# sensors.net
KiCad netlist of a schematic drawn in EAGLE
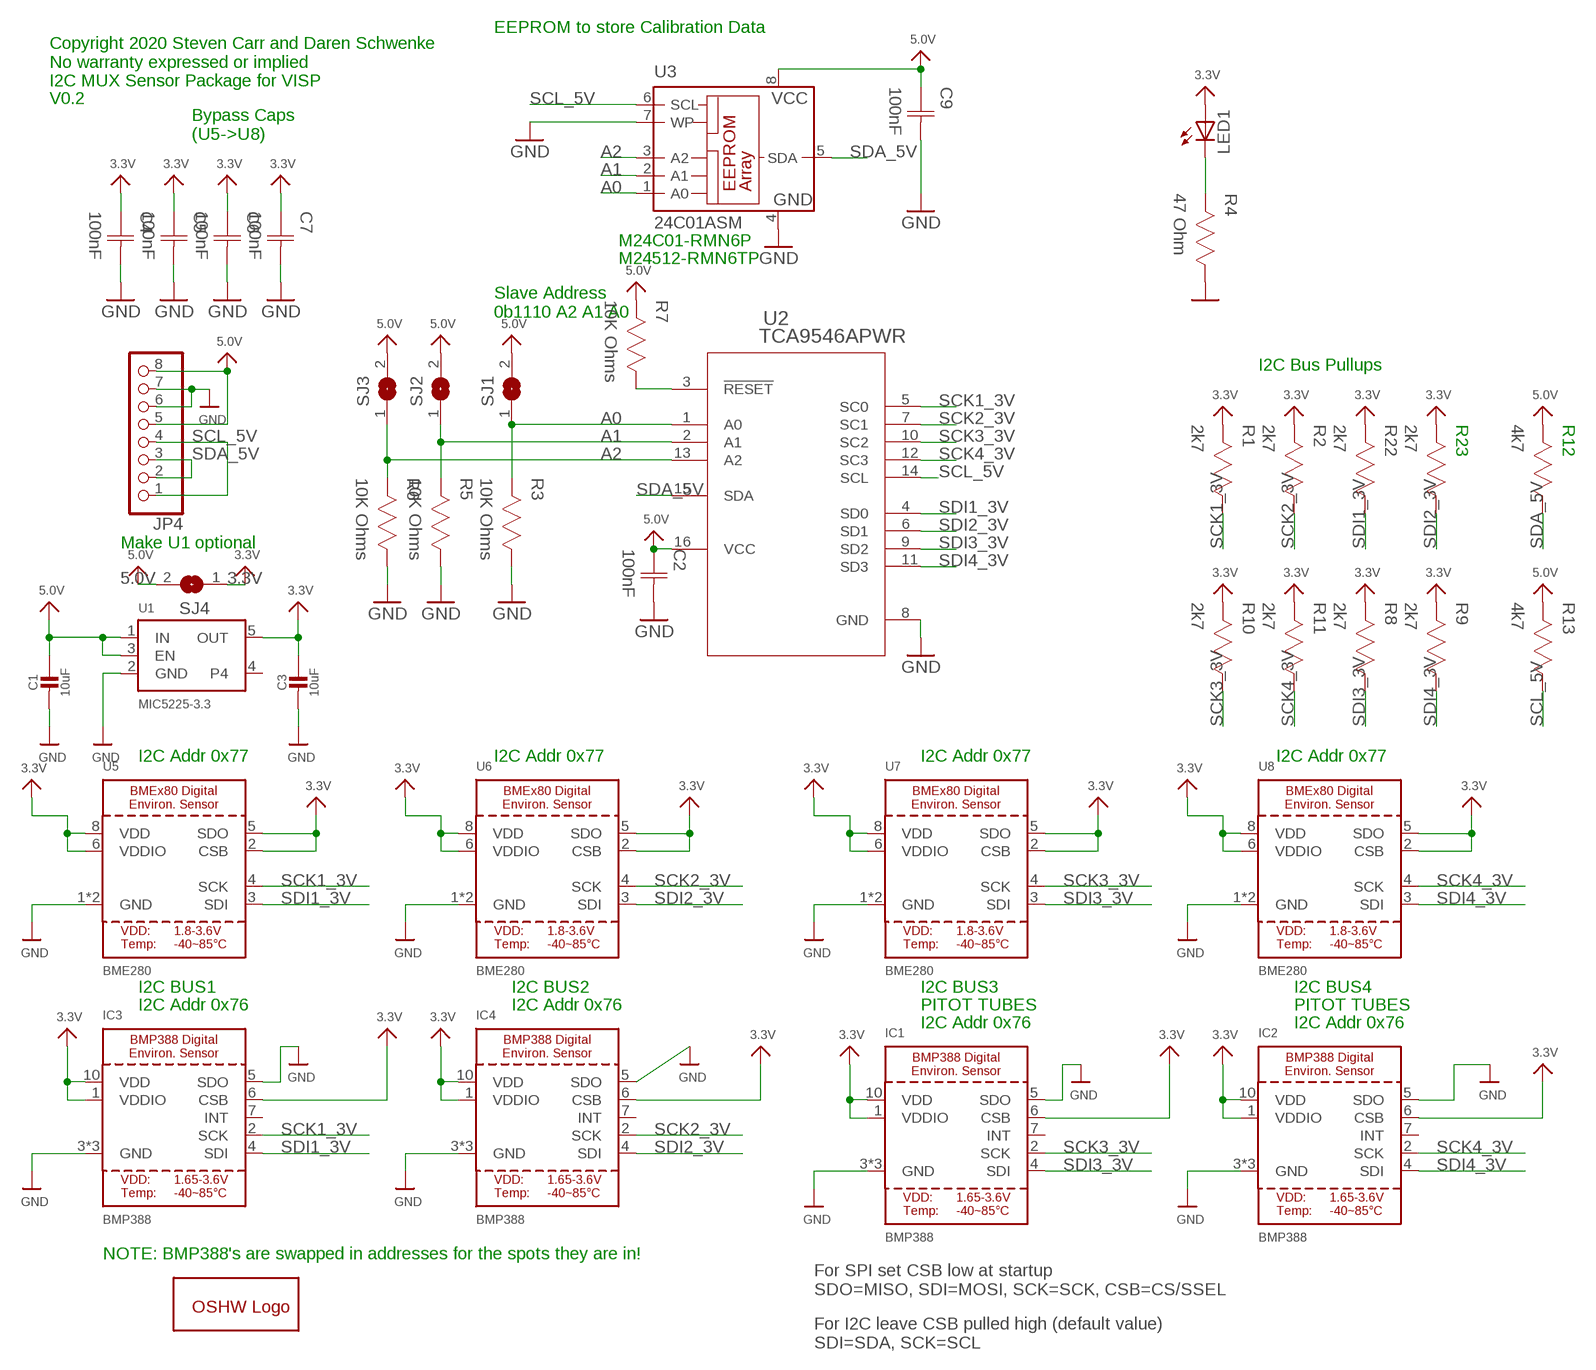
[diagram p0: schematic, sheet 1]

(export (version "E")
  (design (tool "Eeschema 10.0.6"))
  (components
    (comp (ref "C1")
      (value "10uF")
      (footprint "eagle-import:_0805")
      (fields (field (name "MPN") "C1608X5R1A106M080AC"))
      (libsource (lib "eagle-import") (part "CAP_CERAMIC_0805"))
    )
    (comp (ref "C2")
      (value "100nF")
      (footprint "eagle-import:CAP0402")
      (fields (field (name "MPN") "CL10B104KB8NNNC"))
      (libsource (lib "eagle-import") (part "CAPACITOR-0402"))
    )
    (comp (ref "C3")
      (value "10uF")
      (footprint "eagle-import:_0805")
      (fields (field (name "MPN") "C1608X5R1A106M080AC"))
      (libsource (lib "eagle-import") (part "CAP_CERAMIC_0805"))
    )
    (comp (ref "C4")
      (value "100nF")
      (footprint "eagle-import:CAP0402")
      (fields (field (name "MPN") " CL10F104ZO8NNNC "))
      (libsource (lib "eagle-import") (part "CAPACITOR-0402"))
    )
    (comp (ref "C5")
      (value "100nF")
      (footprint "eagle-import:CAP0402")
      (fields (field (name "MPN") " CL10F104ZO8NNNC "))
      (libsource (lib "eagle-import") (part "CAPACITOR-0402"))
    )
    (comp (ref "C6")
      (value "100nF")
      (footprint "eagle-import:CAP0402")
      (fields (field (name "MPN") " CL10F104ZO8NNNC "))
      (libsource (lib "eagle-import") (part "CAPACITOR-0402"))
    )
    (comp (ref "C7")
      (value "100nF")
      (footprint "eagle-import:CAP0402")
      (fields (field (name "MPN") " CL10F104ZO8NNNC "))
      (libsource (lib "eagle-import") (part "CAPACITOR-0402"))
    )
    (comp (ref "C9")
      (value "100nF")
      (footprint "eagle-import:CAP0402")
      (fields (field (name "MPN") "CL10B104KB8NNNC"))
      (libsource (lib "eagle-import") (part "CAPACITOR-0402"))
    )
    (comp (ref "GOLD_ORB_SM1")
      (value "OSHWLOGOLOGO8MM")
      (footprint "eagle-import:OSHW_8MM")
      (libsource (lib "eagle-import") (part "OSHWLOGOLOGO8MM"))
    )
    (comp (ref "IC1")
      (value "BMP388")
      (footprint "eagle-import:BMP388")
      (libsource (lib "eagle-import") (part "BMP388"))
    )
    (comp (ref "IC2")
      (value "BMP388")
      (footprint "eagle-import:BMP388")
      (libsource (lib "eagle-import") (part "BMP388"))
    )
    (comp (ref "IC3")
      (value "BMP388")
      (footprint "eagle-import:BMP388")
      (libsource (lib "eagle-import") (part "BMP388"))
    )
    (comp (ref "IC4")
      (value "BMP388")
      (footprint "eagle-import:BMP388")
      (libsource (lib "eagle-import") (part "BMP388"))
    )
    (comp (ref "JP4")
      (value "PINHD-1X08_2.54")
      (footprint "eagle-import:1X08")
      (libsource (lib "eagle-import") (part "PINHD-1X08_2.54"))
    )
    (comp (ref "LED1")
      (value "LEDCHIP-LED0603")
      (footprint "eagle-import:CHIP-LED0603")
      (fields (field (name "MPN") "SML-D12P8WT86"))
      (libsource (lib "eagle-import") (part "LEDCHIP-LED0603"))
    )
    (comp (ref "R1")
      (value "2k7")
      (footprint "eagle-import:RES0402")
      (fields (field (name "MPN") "CRCW060310K0FKEAC"))
      (libsource (lib "eagle-import") (part "RESISTOR-0402"))
    )
    (comp (ref "R2")
      (value "2k7")
      (footprint "eagle-import:RES0402")
      (fields (field (name "MPN") "CRCW060310K0FKEAC"))
      (libsource (lib "eagle-import") (part "RESISTOR-0402"))
    )
    (comp (ref "R3")
      (value "10K Ohms")
      (footprint "eagle-import:RES0402")
      (fields (field (name "MPN") "CRCW060310K0FKEAC"))
      (libsource (lib "eagle-import") (part "RESISTOR-0402"))
    )
    (comp (ref "R4")
      (value "47 Ohm")
      (footprint "eagle-import:RES0402")
      (fields (field (name "MPN") "RC0603FR-0747RL"))
      (libsource (lib "eagle-import") (part "RESISTOR-0402"))
    )
    (comp (ref "R5")
      (value "10K Ohms")
      (footprint "eagle-import:RES0402")
      (fields (field (name "MPN") "CRCW060310K0FKEAC"))
      (libsource (lib "eagle-import") (part "RESISTOR-0402"))
    )
    (comp (ref "R6")
      (value "10K Ohms")
      (footprint "eagle-import:RES0402")
      (fields (field (name "MPN") "CRCW060310K0FKEAC"))
      (libsource (lib "eagle-import") (part "RESISTOR-0402"))
    )
    (comp (ref "R7")
      (value "10K Ohms")
      (footprint "eagle-import:RES0402")
      (fields (field (name "MPN") "CRCW060310K0FKEAC"))
      (libsource (lib "eagle-import") (part "RESISTOR-0402"))
    )
    (comp (ref "R8")
      (value "2k7")
      (footprint "eagle-import:RES0402")
      (fields (field (name "MPN") "CRCW060310K0FKEAC"))
      (libsource (lib "eagle-import") (part "RESISTOR-0402"))
    )
    (comp (ref "R9")
      (value "2k7")
      (footprint "eagle-import:RES0402")
      (fields (field (name "MPN") "CRCW060310K0FKEAC"))
      (libsource (lib "eagle-import") (part "RESISTOR-0402"))
    )
    (comp (ref "R10")
      (value "2k7")
      (footprint "eagle-import:RES0402")
      (fields (field (name "MPN") "CRCW060310K0FKEAC"))
      (libsource (lib "eagle-import") (part "RESISTOR-0402"))
    )
    (comp (ref "R11")
      (value "2k7")
      (footprint "eagle-import:RES0402")
      (fields (field (name "MPN") "CRCW060310K0FKEAC"))
      (libsource (lib "eagle-import") (part "RESISTOR-0402"))
    )
    (comp (ref "R12")
      (value "4k7")
      (footprint "eagle-import:RES0402")
      (fields (field (name "MPN") "CRCW060310K0FKEAC"))
      (libsource (lib "eagle-import") (part "RESISTOR-0402"))
    )
    (comp (ref "R13")
      (value "4k7")
      (footprint "eagle-import:RES0402")
      (fields (field (name "MPN") "CRCW060310K0FKEAC"))
      (libsource (lib "eagle-import") (part "RESISTOR-0402"))
    )
    (comp (ref "R22")
      (value "2k7")
      (footprint "eagle-import:RES0402")
      (fields (field (name "MPN") "CRCW060310K0FKEAC"))
      (libsource (lib "eagle-import") (part "RESISTOR-0402"))
    )
    (comp (ref "R23")
      (value "2k7")
      (footprint "eagle-import:RES0402")
      (fields (field (name "MPN") "CRCW060310K0FKEAC"))
      (libsource (lib "eagle-import") (part "RESISTOR-0402"))
    )
    (comp (ref "SJ1") (value "SJ") (footprint "eagle-import:SJ") (libsource (lib "eagle-import") (part "SJ")))
    (comp (ref "SJ2") (value "SJ") (footprint "eagle-import:SJ") (libsource (lib "eagle-import") (part "SJ")))
    (comp (ref "SJ3") (value "SJ") (footprint "eagle-import:SJ") (libsource (lib "eagle-import") (part "SJ")))
    (comp (ref "SJ4") (value "SJ") (footprint "eagle-import:SJ") (libsource (lib "eagle-import") (part "SJ")))
    (comp (ref "U1")
      (value "MIC5225-3.3")
      (footprint "eagle-import:SOT23-5")
      (fields (field (name "MPN") "MIC5225-3.3YM5-TR"))
      (libsource (lib "eagle-import") (part "VREG_SOT23-5"))
    )
    (comp (ref "U2")
      (value "TCA9546APWR")
      (footprint "eagle-import:PW16")
      (libsource (lib "eagle-import") (part "TCA9546APWR"))
    )
    (comp (ref "U3")
      (value "24C01ASM")
      (footprint "eagle-import:SO-08M")
      (fields
        (field (name "MF") "MICROCHIP")
        (field (name "MPN") "24C01C/SN")
        (field (name "MPN_1") "M24C01-RMN6P")
      )
      (libsource (lib "eagle-import") (part "24SMC01A"))
    )
    (comp (ref "U5")
      (value "BME280")
      (footprint "eagle-import:BME280")
      (libsource (lib "eagle-import") (part "BME280"))
    )
    (comp (ref "U6")
      (value "BME280")
      (footprint "eagle-import:BME280")
      (libsource (lib "eagle-import") (part "BME280"))
    )
    (comp (ref "U7")
      (value "BME280")
      (footprint "eagle-import:BME280")
      (libsource (lib "eagle-import") (part "BME280"))
    )
    (comp (ref "U8")
      (value "BME280")
      (footprint "eagle-import:BME280")
      (libsource (lib "eagle-import") (part "BME280"))
    )
  )
  (nets
    (net (code "1") (name "/A0") (class "Default")
      (node (ref "R3") (pin "2") (pinfunction "2_2") (pintype "passive"))
      (node (ref "SJ1") (pin "1") (pinfunction "1_1") (pintype "passive"))
      (node (ref "U2") (pin "1") (pinfunction "A0_1") (pintype "input"))
      (node (ref "U3") (pin "1") (pinfunction "A0_1") (pintype "input"))
    )
    (net (code "2") (name "/A1") (class "Default")
      (node (ref "R5") (pin "2") (pinfunction "2_2") (pintype "passive"))
      (node (ref "SJ2") (pin "1") (pinfunction "1_1") (pintype "passive"))
      (node (ref "U2") (pin "2") (pinfunction "A1_2") (pintype "input"))
      (node (ref "U3") (pin "2") (pinfunction "A1_2") (pintype "input"))
    )
    (net (code "3") (name "/A2") (class "Default")
      (node (ref "R6") (pin "2") (pinfunction "2_2") (pintype "passive"))
      (node (ref "SJ3") (pin "1") (pinfunction "1_1") (pintype "passive"))
      (node (ref "U2") (pin "13") (pinfunction "A2_13") (pintype "input"))
      (node (ref "U3") (pin "3") (pinfunction "A2_3") (pintype "input"))
    )
    (net (code "4") (name "/SCK1_3V") (class "Default")
      (node (ref "IC3") (pin "2") (pinfunction "SCK_2") (pintype "input"))
      (node (ref "R1") (pin "1") (pinfunction "1_1") (pintype "passive"))
      (node (ref "U2") (pin "5") (pinfunction "SC0_5") (pintype "passive"))
      (node (ref "U5") (pin "4") (pinfunction "SCK_4") (pintype "input"))
    )
    (net (code "5") (name "/SCK2_3V") (class "Default")
      (node (ref "IC4") (pin "2") (pinfunction "SCK_2") (pintype "input"))
      (node (ref "R2") (pin "1") (pinfunction "1_1") (pintype "passive"))
      (node (ref "U2") (pin "7") (pinfunction "SC1_7") (pintype "passive"))
      (node (ref "U6") (pin "4") (pinfunction "SCK_4") (pintype "input"))
    )
    (net (code "6") (name "/SCK3_3V") (class "Default")
      (node (ref "IC1") (pin "2") (pinfunction "SCK_2") (pintype "input"))
      (node (ref "R10") (pin "1") (pinfunction "1_1") (pintype "passive"))
      (node (ref "U2") (pin "10") (pinfunction "SC2_10") (pintype "passive"))
      (node (ref "U7") (pin "4") (pinfunction "SCK_4") (pintype "input"))
    )
    (net (code "7") (name "/SCK4_3V") (class "Default")
      (node (ref "IC2") (pin "2") (pinfunction "SCK_2") (pintype "input"))
      (node (ref "R11") (pin "1") (pinfunction "1_1") (pintype "passive"))
      (node (ref "U2") (pin "12") (pinfunction "SC3_12") (pintype "passive"))
      (node (ref "U8") (pin "4") (pinfunction "SCK_4") (pintype "input"))
    )
    (net (code "8") (name "/SCL_5V") (class "Default")
      (node (ref "JP4") (pin "1") (pinfunction "1_1") (pintype "passive"))
      (node (ref "JP4") (pin "4") (pinfunction "4_4") (pintype "passive"))
      (node (ref "R13") (pin "1") (pinfunction "1_1") (pintype "passive"))
      (node (ref "U2") (pin "14") (pinfunction "SCL_14") (pintype "passive"))
      (node (ref "U3") (pin "6") (pinfunction "SCL_6") (pintype "input"))
    )
    (net (code "9") (name "/SDA_5V") (class "Default")
      (node (ref "JP4") (pin "2") (pinfunction "2_2") (pintype "passive"))
      (node (ref "JP4") (pin "3") (pinfunction "3_3") (pintype "passive"))
      (node (ref "R12") (pin "1") (pinfunction "1_1") (pintype "passive"))
      (node (ref "U2") (pin "15") (pinfunction "SDA_15") (pintype "passive"))
      (node (ref "U3") (pin "5") (pinfunction "SDA_5") (pintype "bidirectional"))
    )
    (net (code "10") (name "/SDI1_3V") (class "Default")
      (node (ref "IC3") (pin "4") (pinfunction "SDI_4") (pintype "input"))
      (node (ref "R22") (pin "1") (pinfunction "1_1") (pintype "passive"))
      (node (ref "U2") (pin "4") (pinfunction "SD0_4") (pintype "passive"))
      (node (ref "U5") (pin "3") (pinfunction "SDI_3") (pintype "input"))
    )
    (net (code "11") (name "/SDI2_3V") (class "Default")
      (node (ref "IC4") (pin "4") (pinfunction "SDI_4") (pintype "input"))
      (node (ref "R23") (pin "1") (pinfunction "1_1") (pintype "passive"))
      (node (ref "U2") (pin "6") (pinfunction "SD1_6") (pintype "passive"))
      (node (ref "U6") (pin "3") (pinfunction "SDI_3") (pintype "input"))
    )
    (net (code "12") (name "/SDI3_3V") (class "Default")
      (node (ref "IC1") (pin "4") (pinfunction "SDI_4") (pintype "input"))
      (node (ref "R8") (pin "1") (pinfunction "1_1") (pintype "passive"))
      (node (ref "U2") (pin "9") (pinfunction "SD2_9") (pintype "passive"))
      (node (ref "U7") (pin "3") (pinfunction "SDI_3") (pintype "input"))
    )
    (net (code "13") (name "/SDI4_3V") (class "Default")
      (node (ref "IC2") (pin "4") (pinfunction "SDI_4") (pintype "input"))
      (node (ref "R9") (pin "1") (pinfunction "1_1") (pintype "passive"))
      (node (ref "U2") (pin "11") (pinfunction "SD3_11") (pintype "passive"))
      (node (ref "U8") (pin "3") (pinfunction "SDI_3") (pintype "input"))
    )
    (net (code "14") (name "3.3V") (class "Default")
      (node (ref "C3") (pin "1") (pinfunction "1_1") (pintype "passive"))
      (node (ref "C4") (pin "1") (pinfunction "C1_1") (pintype "passive"))
      (node (ref "C5") (pin "1") (pinfunction "C1_1") (pintype "passive"))
      (node (ref "C6") (pin "1") (pinfunction "C1_1") (pintype "passive"))
      (node (ref "C7") (pin "1") (pinfunction "C1_1") (pintype "passive"))
      (node (ref "IC1") (pin "1") (pinfunction "VDDIO_1") (pintype "power_in"))
      (node (ref "IC1") (pin "10") (pinfunction "VDD_10") (pintype "power_in"))
      (node (ref "IC1") (pin "6") (pinfunction "CSB_6") (pintype "input"))
      (node (ref "IC2") (pin "1") (pinfunction "VDDIO_1") (pintype "power_in"))
      (node (ref "IC2") (pin "10") (pinfunction "VDD_10") (pintype "power_in"))
      (node (ref "IC2") (pin "6") (pinfunction "CSB_6") (pintype "input"))
      (node (ref "IC3") (pin "1") (pinfunction "VDDIO_1") (pintype "power_in"))
      (node (ref "IC3") (pin "10") (pinfunction "VDD_10") (pintype "power_in"))
      (node (ref "IC3") (pin "6") (pinfunction "CSB_6") (pintype "input"))
      (node (ref "IC4") (pin "1") (pinfunction "VDDIO_1") (pintype "power_in"))
      (node (ref "IC4") (pin "10") (pinfunction "VDD_10") (pintype "power_in"))
      (node (ref "IC4") (pin "6") (pinfunction "CSB_6") (pintype "input"))
      (node (ref "LED1") (pin "A") (pinfunction "A_A") (pintype "passive"))
      (node (ref "R1") (pin "2") (pinfunction "2_2") (pintype "passive"))
      (node (ref "R10") (pin "2") (pinfunction "2_2") (pintype "passive"))
      (node (ref "R11") (pin "2") (pinfunction "2_2") (pintype "passive"))
      (node (ref "R2") (pin "2") (pinfunction "2_2") (pintype "passive"))
      (node (ref "R22") (pin "2") (pinfunction "2_2") (pintype "passive"))
      (node (ref "R23") (pin "2") (pinfunction "2_2") (pintype "passive"))
      (node (ref "R8") (pin "2") (pinfunction "2_2") (pintype "passive"))
      (node (ref "R9") (pin "2") (pinfunction "2_2") (pintype "passive"))
      (node (ref "SJ4") (pin "1") (pinfunction "1_1") (pintype "passive"))
      (node (ref "U1") (pin "5") (pinfunction "OUT_5") (pintype "power_in"))
      (node (ref "U5") (pin "2") (pinfunction "CSB_2") (pintype "input"))
      (node (ref "U5") (pin "5") (pinfunction "SDO_5") (pintype "output"))
      (node (ref "U5") (pin "6") (pinfunction "VDDIO_6") (pintype "power_in"))
      (node (ref "U5") (pin "8") (pinfunction "VDD_8") (pintype "power_in"))
      (node (ref "U6") (pin "2") (pinfunction "CSB_2") (pintype "input"))
      (node (ref "U6") (pin "5") (pinfunction "SDO_5") (pintype "output"))
      (node (ref "U6") (pin "6") (pinfunction "VDDIO_6") (pintype "power_in"))
      (node (ref "U6") (pin "8") (pinfunction "VDD_8") (pintype "power_in"))
      (node (ref "U7") (pin "2") (pinfunction "CSB_2") (pintype "input"))
      (node (ref "U7") (pin "5") (pinfunction "SDO_5") (pintype "output"))
      (node (ref "U7") (pin "6") (pinfunction "VDDIO_6") (pintype "power_in"))
      (node (ref "U7") (pin "8") (pinfunction "VDD_8") (pintype "power_in"))
      (node (ref "U8") (pin "2") (pinfunction "CSB_2") (pintype "input"))
      (node (ref "U8") (pin "5") (pinfunction "SDO_5") (pintype "output"))
      (node (ref "U8") (pin "6") (pinfunction "VDDIO_6") (pintype "power_in"))
      (node (ref "U8") (pin "8") (pinfunction "VDD_8") (pintype "power_in"))
    )
    (net (code "15") (name "5.0V") (class "Default")
      (node (ref "C1") (pin "1") (pinfunction "1_1") (pintype "passive"))
      (node (ref "C2") (pin "1") (pinfunction "C1_1") (pintype "passive"))
      (node (ref "C9") (pin "1") (pinfunction "C1_1") (pintype "passive"))
      (node (ref "JP4") (pin "5") (pinfunction "5_5") (pintype "passive"))
      (node (ref "JP4") (pin "8") (pinfunction "8_8") (pintype "passive"))
      (node (ref "R12") (pin "2") (pinfunction "2_2") (pintype "passive"))
      (node (ref "R13") (pin "2") (pinfunction "2_2") (pintype "passive"))
      (node (ref "R7") (pin "2") (pinfunction "2_2") (pintype "passive"))
      (node (ref "SJ1") (pin "2") (pinfunction "2_2") (pintype "passive"))
      (node (ref "SJ2") (pin "2") (pinfunction "2_2") (pintype "passive"))
      (node (ref "SJ3") (pin "2") (pinfunction "2_2") (pintype "passive"))
      (node (ref "SJ4") (pin "2") (pinfunction "2_2") (pintype "passive"))
      (node (ref "U1") (pin "1") (pinfunction "IN_1") (pintype "power_in"))
      (node (ref "U1") (pin "3") (pinfunction "EN_3") (pintype "input"))
      (node (ref "U2") (pin "16") (pinfunction "VCC_16") (pintype "power_in"))
      (node (ref "U3") (pin "8") (pinfunction "VCC_8") (pintype "power_in"))
    )
    (net (code "16") (name "GND") (class "Default")
      (node (ref "C1") (pin "2") (pinfunction "2_2") (pintype "passive"))
      (node (ref "C2") (pin "2") (pinfunction "C2_2") (pintype "passive"))
      (node (ref "C3") (pin "2") (pinfunction "2_2") (pintype "passive"))
      (node (ref "C4") (pin "2") (pinfunction "C2_2") (pintype "passive"))
      (node (ref "C5") (pin "2") (pinfunction "C2_2") (pintype "passive"))
      (node (ref "C6") (pin "2") (pinfunction "C2_2") (pintype "passive"))
      (node (ref "C7") (pin "2") (pinfunction "C2_2") (pintype "passive"))
      (node (ref "C9") (pin "2") (pinfunction "C2_2") (pintype "passive"))
      (node (ref "IC1") (pin "3") (pinfunction "GND_3") (pintype "power_in"))
      (node (ref "IC1") (pin "5") (pinfunction "SDO_5") (pintype "output"))
      (node (ref "IC1") (pin "8") (pinfunction "GND_8") (pintype "power_in"))
      (node (ref "IC1") (pin "9") (pinfunction "GND_9") (pintype "power_in"))
      (node (ref "IC2") (pin "3") (pinfunction "GND_3") (pintype "power_in"))
      (node (ref "IC2") (pin "5") (pinfunction "SDO_5") (pintype "output"))
      (node (ref "IC2") (pin "8") (pinfunction "GND_8") (pintype "power_in"))
      (node (ref "IC2") (pin "9") (pinfunction "GND_9") (pintype "power_in"))
      (node (ref "IC3") (pin "3") (pinfunction "GND_3") (pintype "power_in"))
      (node (ref "IC3") (pin "5") (pinfunction "SDO_5") (pintype "output"))
      (node (ref "IC3") (pin "8") (pinfunction "GND_8") (pintype "power_in"))
      (node (ref "IC3") (pin "9") (pinfunction "GND_9") (pintype "power_in"))
      (node (ref "IC4") (pin "3") (pinfunction "GND_3") (pintype "power_in"))
      (node (ref "IC4") (pin "5") (pinfunction "SDO_5") (pintype "output"))
      (node (ref "IC4") (pin "8") (pinfunction "GND_8") (pintype "power_in"))
      (node (ref "IC4") (pin "9") (pinfunction "GND_9") (pintype "power_in"))
      (node (ref "JP4") (pin "6") (pinfunction "6_6") (pintype "passive"))
      (node (ref "JP4") (pin "7") (pinfunction "7_7") (pintype "passive"))
      (node (ref "R3") (pin "1") (pinfunction "1_1") (pintype "passive"))
      (node (ref "R4") (pin "1") (pinfunction "1_1") (pintype "passive"))
      (node (ref "R5") (pin "1") (pinfunction "1_1") (pintype "passive"))
      (node (ref "R6") (pin "1") (pinfunction "1_1") (pintype "passive"))
      (node (ref "U1") (pin "2") (pinfunction "GND_2") (pintype "power_in"))
      (node (ref "U2") (pin "8") (pinfunction "GND_8") (pintype "power_in"))
      (node (ref "U3") (pin "4") (pinfunction "GND_4") (pintype "power_in"))
      (node (ref "U3") (pin "7") (pinfunction "WP_7") (pintype "input"))
      (node (ref "U5") (pin "1") (pinfunction "GND_1") (pintype "power_in"))
      (node (ref "U5") (pin "7") (pinfunction "GND_7") (pintype "power_in"))
      (node (ref "U6") (pin "1") (pinfunction "GND_1") (pintype "power_in"))
      (node (ref "U6") (pin "7") (pinfunction "GND_7") (pintype "power_in"))
      (node (ref "U7") (pin "1") (pinfunction "GND_1") (pintype "power_in"))
      (node (ref "U7") (pin "7") (pinfunction "GND_7") (pintype "power_in"))
      (node (ref "U8") (pin "1") (pinfunction "GND_1") (pintype "power_in"))
      (node (ref "U8") (pin "7") (pinfunction "GND_7") (pintype "power_in"))
    )
    (net (code "17") (name "Net-(LED1-PadC)") (class "Default")
      (node (ref "LED1") (pin "C") (pinfunction "C_C") (pintype "passive"))
      (node (ref "R4") (pin "2") (pinfunction "2_2") (pintype "passive"))
    )
    (net (code "18") (name "Net-(U2-~{RESET})") (class "Default")
      (node (ref "R7") (pin "1") (pinfunction "1_1") (pintype "passive"))
      (node (ref "U2") (pin "3") (pinfunction "~{RESET}_3") (pintype "input"))
    )
    (net (code "19") (name "unconnected-(IC1-INT-Pad7)") (class "Default")
      (node (ref "IC1") (pin "7") (pinfunction "INT_7") (pintype "output"))
    )
    (net (code "20") (name "unconnected-(IC2-INT-Pad7)") (class "Default")
      (node (ref "IC2") (pin "7") (pinfunction "INT_7") (pintype "output"))
    )
    (net (code "21") (name "unconnected-(IC3-INT-Pad7)") (class "Default")
      (node (ref "IC3") (pin "7") (pinfunction "INT_7") (pintype "output"))
    )
    (net (code "22") (name "unconnected-(IC4-INT-Pad7)") (class "Default")
      (node (ref "IC4") (pin "7") (pinfunction "INT_7") (pintype "output"))
    )
    (net (code "23") (name "unconnected-(U1-P4-Pad4)") (class "Default")
      (node (ref "U1") (pin "4") (pinfunction "P4_4") (pintype "bidirectional"))
    )
  )
)
